# SCH_SX1262_Antenna.net
KiCad netlist of a schematic drawn in Altium Designer
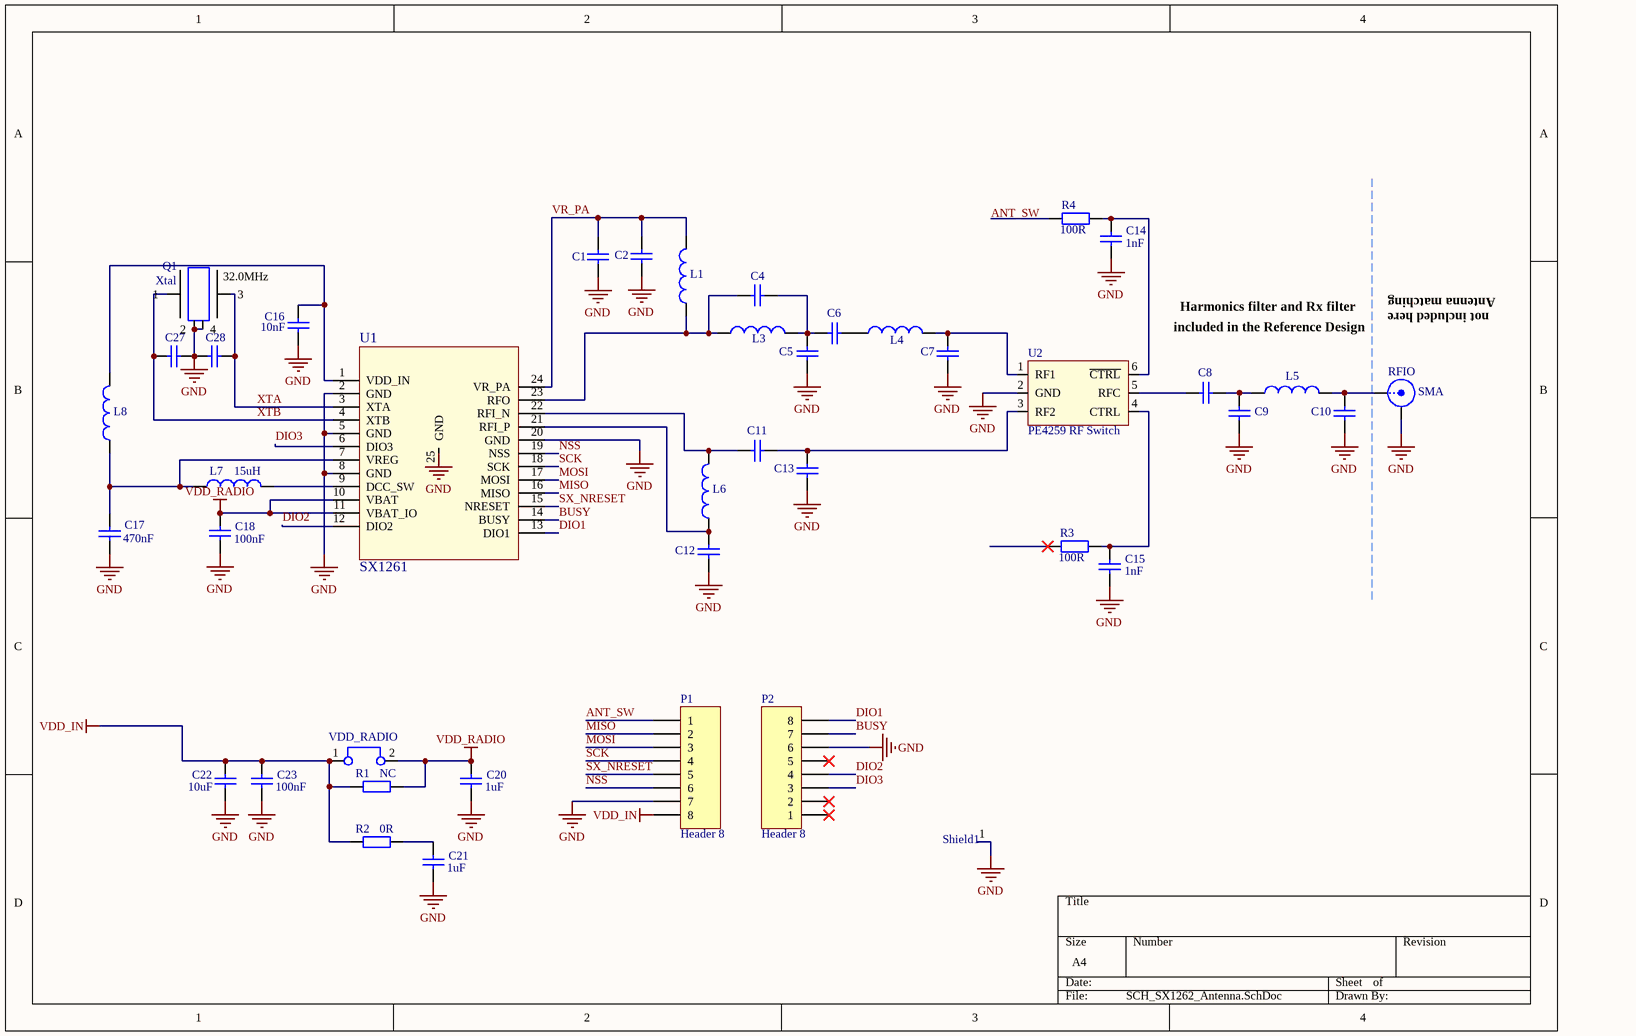
[diagram p0: SCH_SX1262_Antenna.SchDoc]

(export (version "E")
  (design (tool "Eeschema 10.0.6"))
  (components
    (comp (ref "C1")
      (value "Cap")
      (footprint "rlc_402_smd")
      (description "Capacitor SMD")
      (fields (field (name "PUBLISHER") "Altium Limited"))
      (libsource (lib "SX1261MB2xAS_e498v01a") (part "Cap"))
    )
    (comp (ref "C2")
      (value "Cap")
      (footprint "rlc_402_smd")
      (description "Capacitor SMD")
      (fields (field (name "PUBLISHER") "Altium Limited"))
      (libsource (lib "SX1261MB2xAS_e498v01a") (part "Cap"))
    )
    (comp (ref "C4")
      (value "Cap")
      (footprint "rlc_402_smd")
      (description "Capacitor SMD")
      (fields (field (name "PUBLISHER") "Altium Limited"))
      (libsource (lib "SX1261MB2xAS_e498v01a") (part "Cap"))
    )
    (comp (ref "C5")
      (value "Cap")
      (footprint "rlc_402_smd")
      (description "Capacitor SMD")
      (fields (field (name "PUBLISHER") "Altium Limited"))
      (libsource (lib "SX1261MB2xAS_e498v01a") (part "Cap"))
    )
    (comp (ref "C6")
      (value "Cap")
      (footprint "rlc_402_smd")
      (description "Capacitor SMD")
      (fields (field (name "PUBLISHER") "Altium Limited"))
      (libsource (lib "SX1261MB2xAS_e498v01a") (part "Cap"))
    )
    (comp (ref "C7")
      (value "Cap")
      (footprint "rlc_402_smd")
      (description "Capacitor SMD")
      (fields (field (name "PUBLISHER") "Altium Limited"))
      (libsource (lib "SX1261MB2xAS_e498v01a") (part "Cap"))
    )
    (comp (ref "C8")
      (value "Cap")
      (footprint "rlc_402_smd")
      (description "Capacitor SMD")
      (fields (field (name "PUBLISHER") "Altium Limited"))
      (libsource (lib "SX1261MB2xAS_e498v01a") (part "Cap"))
    )
    (comp (ref "C9")
      (value "Cap")
      (footprint "rlc_402_smd")
      (description "Capacitor SMD")
      (fields (field (name "PUBLISHER") "Altium Limited"))
      (libsource (lib "SX1261MB2xAS_e498v01a") (part "Cap"))
    )
    (comp (ref "C10")
      (value "Cap")
      (footprint "rlc_402_smd")
      (description "Capacitor SMD")
      (fields (field (name "PUBLISHER") "Altium Limited"))
      (libsource (lib "SX1261MB2xAS_e498v01a") (part "Cap"))
    )
    (comp (ref "C11")
      (value "Cap")
      (footprint "rlc_402_smd")
      (description "Capacitor SMD")
      (fields (field (name "PUBLISHER") "Altium Limited"))
      (libsource (lib "SX1261MB2xAS_e498v01a") (part "Cap"))
    )
    (comp (ref "C12")
      (value "Cap")
      (footprint "rlc_402_smd")
      (description "Capacitor SMD")
      (fields (field (name "PUBLISHER") "Altium Limited"))
      (libsource (lib "SX1261MB2xAS_e498v01a") (part "Cap"))
    )
    (comp (ref "C13")
      (value "Cap")
      (footprint "rlc_402_smd")
      (description "Capacitor SMD")
      (fields (field (name "PUBLISHER") "Altium Limited"))
      (libsource (lib "SX1261MB2xAS_e498v01a") (part "Cap"))
    )
    (comp (ref "C14")
      (value "1nF")
      (footprint "rlc_402_smd")
      (description "Capacitor SMD")
      (fields (field (name "Comment") "Cap") (field (name "PUBLISHER") "Altium Limited"))
      (libsource (lib "SX1261MB2xAS_e498v01a") (part "Cap"))
    )
    (comp (ref "C15")
      (value "1nF")
      (footprint "rlc_402_smd")
      (description "Capacitor SMD")
      (fields (field (name "Comment") "Cap") (field (name "PUBLISHER") "Altium Limited"))
      (libsource (lib "SX1261MB2xAS_e498v01a") (part "Cap"))
    )
    (comp (ref "C16")
      (value "10nF")
      (footprint "rlc_402_smd")
      (description "Capacitor SMD")
      (fields (field (name "Comment") "Cap") (field (name "PUBLISHER") "Altium Limited"))
      (libsource (lib "SX1261MB2xAS_e498v01a") (part "Cap"))
    )
    (comp (ref "C17")
      (value "470nF")
      (footprint "rlc_402_smd")
      (description "Capacitor SMD")
      (fields (field (name "Comment") "Cap") (field (name "PUBLISHER") "Altium Limited"))
      (libsource (lib "SX1261MB2xAS_e498v01a") (part "Cap"))
    )
    (comp (ref "C18")
      (value "100nF")
      (footprint "rlc_402_smd")
      (description "Capacitor SMD")
      (fields (field (name "Comment") "Cap") (field (name "PUBLISHER") "Altium Limited"))
      (libsource (lib "SX1261MB2xAS_e498v01a") (part "Cap"))
    )
    (comp (ref "C20")
      (value "1uF")
      (footprint "rlc_603_smd")
      (description "Capacitor SMD")
      (fields (field (name "Comment") "Cap") (field (name "PUBLISHER") "Altium Limited"))
      (libsource (lib "SX1261_e406v03a") (part "Cap"))
    )
    (comp (ref "C21")
      (value "1uF")
      (footprint "rlc_603_smd")
      (description "Capacitor SMD")
      (fields (field (name "Comment") "Cap") (field (name "PUBLISHER") "Altium Limited"))
      (libsource (lib "SX1261_e406v03a") (part "Cap"))
    )
    (comp (ref "C22")
      (value "10uF")
      (footprint "rlc_805_smd")
      (description "Capacitor SMD")
      (fields (field (name "Comment") "Cap") (field (name "PUBLISHER") "Altium Limited"))
      (libsource (lib "SX1261_e406v03a") (part "Cap"))
    )
    (comp (ref "C23")
      (value "100nF")
      (footprint "rlc_402_smd")
      (description "Capacitor SMD")
      (fields (field (name "Comment") "Cap") (field (name "PUBLISHER") "Altium Limited"))
      (libsource (lib "SX1261_e406v03a") (part "Cap"))
    )
    (comp (ref "C27")
      (value "Cap")
      (footprint "rlc_402_smd")
      (description "Capacitor SMD")
      (fields (field (name "PUBLISHER") "Altium Limited"))
      (libsource (lib "SX1261_e406v03a") (part "Cap"))
    )
    (comp (ref "C28")
      (value "Cap")
      (footprint "rlc_402_smd")
      (description "Capacitor SMD")
      (fields (field (name "PUBLISHER") "Altium Limited"))
      (libsource (lib "SX1261_e406v03a") (part "Cap"))
    )
    (comp (ref "L1")
      (value "Inductor")
      (footprint "rlc_402_smd")
      (description "Inductor SMD")
      (fields (field (name "PUBLISHER") "Altium Limited"))
      (libsource (lib "") (part "Inductor_1"))
    )
    (comp (ref "L3")
      (value "Inductor")
      (footprint "rlc_402_smd")
      (description "Inductor SMD")
      (fields (field (name "PUBLISHER") "Altium Limited"))
      (libsource (lib "") (part "Inductor_1"))
    )
    (comp (ref "L4")
      (value "Inductor")
      (footprint "rlc_402_smd")
      (description "Inductor SMD")
      (fields (field (name "PUBLISHER") "Altium Limited"))
      (libsource (lib "") (part "Inductor_1"))
    )
    (comp (ref "L5")
      (value "Inductor")
      (footprint "rlc_402_smd")
      (description "Inductor SMD")
      (fields (field (name "PUBLISHER") "Altium Limited"))
      (libsource (lib "") (part "Inductor_1"))
    )
    (comp (ref "L6")
      (value "Inductor")
      (footprint "rlc_402_smd")
      (description "Inductor SMD")
      (fields (field (name "PUBLISHER") "Altium Limited"))
      (libsource (lib "") (part "Inductor_1"))
    )
    (comp (ref "L7")
      (value "15uH")
      (footprint "rlc_805_smd enlarged")
      (description "Inductor SMD")
      (fields (field (name "Comment") "Inductor") (field (name "PUBLISHER") "Altium Limited"))
      (libsource (lib "") (part "Inductor_1"))
    )
    (comp (ref "L8")
      (value "Inductor")
      (footprint "rlc_402_smd")
      (description "Inductor SMD")
      (fields (field (name "PUBLISHER") "Altium Limited"))
      (libsource (lib "SX1261MB2xAS_e498v01a") (part "Inductor"))
    )
    (comp (ref "P1")
      (value "Header 8")
      (footprint "HDR1X8")
      (description "Header, 8-Pin")
      (fields (field (name "PUBLISHER") "Altium Limited"))
      (libsource (lib "") (part "Header 8_1"))
    )
    (comp (ref "P2")
      (value "Header 8")
      (footprint "HDR1X8")
      (description "Header, 8-Pin")
      (fields (field (name "PUBLISHER") "Altium Limited"))
      (libsource (lib "SX1262_DemoBoard") (part "Header 8"))
    )
    (comp (ref "Q1")
      (value "Xtal")
      (footprint "nd2016da")
      (description "Crystal with GND pins")
      (fields (field (name "ALTIUM_VALUE") "32.0MHz"))
      (libsource (lib "SX1261MB2xAS_e498v01a") (part "Xtal GND"))
    )
    (comp (ref "R1")
      (value "NC")
      (footprint "rlc_603_smd")
      (description "Resistor SMD - IEC symbol version")
      (fields (field (name "Comment") "Resistor"))
      (libsource (lib "SX1261_e406v03a") (part "Resistor"))
    )
    (comp (ref "R2")
      (value "0R")
      (footprint "rlc_603_smd")
      (description "Resistor SMD - IEC symbol version")
      (fields (field (name "Comment") "Resistor"))
      (libsource (lib "SX1261_e406v03a") (part "Resistor"))
    )
    (comp (ref "R3")
      (value "100R")
      (footprint "rlc_402_smd")
      (description "Resistor SMD - IEC symbol version")
      (fields (field (name "Comment") "Resistor"))
      (libsource (lib "SX1261MB2xAS_e498v01a") (part "Resistor"))
    )
    (comp (ref "R4")
      (value "100R")
      (footprint "rlc_402_smd")
      (description "Resistor SMD - IEC symbol version")
      (fields (field (name "Comment") "Resistor"))
      (libsource (lib "SX1261MB2xAS_e498v01a") (part "Resistor"))
    )
    (comp (ref "RFIO")
      (value "SMA")
      (footprint "SMA_end_launch_1.0mm_9.52mm")
      (description "SMA Straight Connector")
      (fields (field (name "PUBLISHER") "Altium Limited"))
      (libsource (lib "SX1261_e406v03a") (part "SMA"))
    )
    (comp (ref "Shield1")
      (value "Logo symbol")
      (footprint "BMIS-209-F - Shield")
      (description "Shield - EMI Gasket - Standard Surface Mount Shields")
      (libsource (lib "SX1261MB2xAS_e498v01a") (part "Shield"))
    )
    (comp (ref "U1")
      (value "SX1261")
      (footprint "vqfn24_4x4mm")
      (description "SX1261/2 - Ultra low power RF transceiver")
      (libsource (lib "SX1261MB2xAS_e498v01a") (part "SX126x"))
    )
    (comp (ref "U2")
      (value "PE4259 RF Switch")
      (footprint "SC70-6")
      (description "PE4259 Peregrine RF Switch")
      (libsource (lib "SX1261MB2xAS_e498v01a") (part "PE4259 RF Switch"))
    )
    (comp (ref "VDD_RADIO")
      (value "Jumper")
      (footprint "bridge_254mm")
      (description "Jumper Wire")
      (libsource (lib "SX1261_e406v03a") (part "Jumper"))
    )
  )
  (nets
    (net (code "1") (name "/ANT_SW") (class "Default")
      (node (ref "P1") (pin "1") (pinfunction "1_1") (pintype "passive"))
    )
    (net (code "2") (name "/BUSY") (class "Default")
      (node (ref "P2") (pin "7") (pinfunction "7_7") (pintype "passive"))
      (node (ref "U1") (pin "14") (pinfunction "BUSY_14") (pintype "passive"))
    )
    (net (code "3") (name "/DIO1") (class "Default")
      (node (ref "P2") (pin "8") (pinfunction "8_8") (pintype "passive"))
      (node (ref "U1") (pin "13") (pinfunction "DIO1_13") (pintype "passive"))
    )
    (net (code "4") (name "/DIO2") (class "Default")
      (node (ref "P2") (pin "4") (pinfunction "4_4") (pintype "passive"))
      (node (ref "U1") (pin "12") (pinfunction "DIO2_12") (pintype "passive"))
    )
    (net (code "5") (name "/DIO3") (class "Default")
      (node (ref "P2") (pin "3") (pinfunction "3_3") (pintype "passive"))
      (node (ref "U1") (pin "6") (pinfunction "DIO3_6") (pintype "passive"))
    )
    (net (code "6") (name "/MISO") (class "Default")
      (node (ref "P1") (pin "2") (pinfunction "2_2") (pintype "passive"))
      (node (ref "U1") (pin "16") (pinfunction "MISO_16") (pintype "passive"))
    )
    (net (code "7") (name "/MOSI") (class "Default")
      (node (ref "P1") (pin "3") (pinfunction "3_3") (pintype "passive"))
      (node (ref "U1") (pin "17") (pinfunction "MOSI_17") (pintype "passive"))
    )
    (net (code "8") (name "/NSS") (class "Default")
      (node (ref "P1") (pin "6") (pinfunction "6_6") (pintype "passive"))
      (node (ref "U1") (pin "19") (pinfunction "NSS_19") (pintype "passive"))
    )
    (net (code "9") (name "/SCK") (class "Default")
      (node (ref "P1") (pin "4") (pinfunction "4_4") (pintype "passive"))
      (node (ref "U1") (pin "18") (pinfunction "SCK_18") (pintype "passive"))
    )
    (net (code "10") (name "/SX_NRESET") (class "Default")
      (node (ref "P1") (pin "5") (pinfunction "5_5") (pintype "passive"))
      (node (ref "U1") (pin "15") (pinfunction "NRESET_15") (pintype "passive"))
    )
    (net (code "11") (name "/VR_PA") (class "Default")
      (node (ref "C1") (pin "2") (pinfunction "2_2") (pintype "passive"))
      (node (ref "C2") (pin "2") (pinfunction "2_2") (pintype "passive"))
      (node (ref "L1") (pin "2") (pinfunction "2_2") (pintype "passive"))
      (node (ref "U1") (pin "24") (pinfunction "VR_PA_24") (pintype "power_in"))
    )
    (net (code "12") (name "/XTA") (class "Default")
      (node (ref "C28") (pin "1") (pinfunction "1_1") (pintype "passive"))
      (node (ref "Q1") (pin "3") (pinfunction "3_3") (pintype "passive"))
      (node (ref "U1") (pin "3") (pinfunction "XTA_3") (pintype "passive"))
    )
    (net (code "13") (name "/XTB") (class "Default")
      (node (ref "C27") (pin "2") (pinfunction "2_2") (pintype "passive"))
      (node (ref "Q1") (pin "1") (pinfunction "1_1") (pintype "passive"))
      (node (ref "U1") (pin "4") (pinfunction "XTB_4") (pintype "passive"))
    )
    (net (code "14") (name "GND") (class "Default")
      (node (ref "C1") (pin "1") (pinfunction "1_1") (pintype "passive"))
      (node (ref "C10") (pin "1") (pinfunction "1_1") (pintype "passive"))
      (node (ref "C12") (pin "1") (pinfunction "1_1") (pintype "passive"))
      (node (ref "C13") (pin "1") (pinfunction "1_1") (pintype "passive"))
      (node (ref "C14") (pin "2") (pinfunction "2_2") (pintype "passive"))
      (node (ref "C15") (pin "2") (pinfunction "2_2") (pintype "passive"))
      (node (ref "C16") (pin "1") (pinfunction "1_1") (pintype "passive"))
      (node (ref "C17") (pin "1") (pinfunction "1_1") (pintype "passive"))
      (node (ref "C18") (pin "1") (pinfunction "1_1") (pintype "passive"))
      (node (ref "C2") (pin "1") (pinfunction "1_1") (pintype "passive"))
      (node (ref "C20") (pin "1") (pinfunction "1_1") (pintype "passive"))
      (node (ref "C21") (pin "1") (pinfunction "1_1") (pintype "passive"))
      (node (ref "C22") (pin "1") (pinfunction "1_1") (pintype "passive"))
      (node (ref "C23") (pin "1") (pinfunction "1_1") (pintype "passive"))
      (node (ref "C27") (pin "1") (pinfunction "1_1") (pintype "passive"))
      (node (ref "C28") (pin "2") (pinfunction "2_2") (pintype "passive"))
      (node (ref "C5") (pin "1") (pinfunction "1_1") (pintype "passive"))
      (node (ref "C7") (pin "1") (pinfunction "1_1") (pintype "passive"))
      (node (ref "C9") (pin "1") (pinfunction "1_1") (pintype "passive"))
      (node (ref "P1") (pin "7") (pinfunction "7_7") (pintype "passive"))
      (node (ref "P2") (pin "6") (pinfunction "6_6") (pintype "passive"))
      (node (ref "Q1") (pin "2") (pinfunction "2_2") (pintype "passive"))
      (node (ref "Q1") (pin "4") (pinfunction "4_4") (pintype "passive"))
      (node (ref "RFIO") (pin "2") (pinfunction "GND_2") (pintype "passive"))
      (node (ref "Shield1") (pin "1") (pinfunction "1_1") (pintype "passive"))
      (node (ref "U1") (pin "2") (pinfunction "GND_2") (pintype "passive"))
      (node (ref "U1") (pin "20") (pinfunction "GND_20") (pintype "passive"))
      (node (ref "U1") (pin "25") (pinfunction "GND_25") (pintype "passive"))
      (node (ref "U1") (pin "5") (pinfunction "GND_5") (pintype "passive"))
      (node (ref "U1") (pin "8") (pinfunction "GND_8") (pintype "passive"))
      (node (ref "U2") (pin "2") (pinfunction "GND_2") (pintype "passive"))
    )
    (net (code "15") (name "Net-(C4-Pad1)") (class "Default")
      (node (ref "C4") (pin "1") (pinfunction "1_1") (pintype "passive"))
      (node (ref "C5") (pin "2") (pinfunction "2_2") (pintype "passive"))
      (node (ref "C6") (pin "2") (pinfunction "2_2") (pintype "passive"))
      (node (ref "L3") (pin "2") (pinfunction "2_2") (pintype "passive"))
    )
    (net (code "16") (name "Net-(C6-Pad1)") (class "Default")
      (node (ref "C6") (pin "1") (pinfunction "1_1") (pintype "passive"))
      (node (ref "L4") (pin "1") (pinfunction "1_1") (pintype "passive"))
    )
    (net (code "17") (name "Net-(C8-Pad1)") (class "Default")
      (node (ref "C8") (pin "1") (pinfunction "1_1") (pintype "passive"))
      (node (ref "C9") (pin "2") (pinfunction "2_2") (pintype "passive"))
      (node (ref "L5") (pin "1") (pinfunction "1_1") (pintype "passive"))
    )
    (net (code "18") (name "Net-(C21-Pad2)") (class "Default")
      (node (ref "C21") (pin "2") (pinfunction "2_2") (pintype "passive"))
      (node (ref "R2") (pin "1") (pinfunction "1_1") (pintype "passive"))
    )
    (net (code "19") (name "Net-(RFIO-Signal)") (class "Default")
      (node (ref "C10") (pin "2") (pinfunction "2_2") (pintype "passive"))
      (node (ref "L5") (pin "2") (pinfunction "2_2") (pintype "passive"))
      (node (ref "RFIO") (pin "1") (pinfunction "Signal_1") (pintype "passive"))
    )
    (net (code "20") (name "Net-(U1-DCC_SW)") (class "Default")
      (node (ref "L7") (pin "2") (pinfunction "2_2") (pintype "passive"))
      (node (ref "U1") (pin "9") (pinfunction "DCC_SW_9") (pintype "power_in"))
    )
    (net (code "21") (name "Net-(U1-RFI_N)") (class "Default")
      (node (ref "C11") (pin "2") (pinfunction "2_2") (pintype "passive"))
      (node (ref "L6") (pin "2") (pinfunction "2_2") (pintype "passive"))
      (node (ref "U1") (pin "22") (pinfunction "RFI_N_22") (pintype "passive"))
    )
    (net (code "22") (name "Net-(U1-RFI_P)") (class "Default")
      (node (ref "C12") (pin "2") (pinfunction "2_2") (pintype "passive"))
      (node (ref "L6") (pin "1") (pinfunction "1_1") (pintype "passive"))
      (node (ref "U1") (pin "21") (pinfunction "RFI_P_21") (pintype "passive"))
    )
    (net (code "23") (name "Net-(U1-RFO)") (class "Default")
      (node (ref "C4") (pin "2") (pinfunction "2_2") (pintype "passive"))
      (node (ref "L1") (pin "1") (pinfunction "1_1") (pintype "passive"))
      (node (ref "L3") (pin "1") (pinfunction "1_1") (pintype "passive"))
      (node (ref "U1") (pin "23") (pinfunction "RFO_23") (pintype "passive"))
    )
    (net (code "24") (name "Net-(U1-VDD_IN)") (class "Default")
      (node (ref "C16") (pin "2") (pinfunction "2_2") (pintype "passive"))
      (node (ref "L8") (pin "1") (pinfunction "1_1") (pintype "passive"))
      (node (ref "U1") (pin "1") (pinfunction "VDD_IN_1") (pintype "power_in"))
    )
    (net (code "25") (name "Net-(U1-VREG)") (class "Default")
      (node (ref "C17") (pin "2") (pinfunction "2_2") (pintype "passive"))
      (node (ref "L7") (pin "1") (pinfunction "1_1") (pintype "passive"))
      (node (ref "L8") (pin "2") (pinfunction "2_2") (pintype "passive"))
      (node (ref "U1") (pin "7") (pinfunction "VREG_7") (pintype "power_in"))
    )
    (net (code "26") (name "Net-(U2-CTRL)") (class "Default")
      (node (ref "C15") (pin "1") (pinfunction "1_1") (pintype "passive"))
      (node (ref "R3") (pin "1") (pinfunction "1_1") (pintype "passive"))
      (node (ref "U2") (pin "4") (pinfunction "CTRL_4") (pintype "passive"))
    )
    (net (code "27") (name "Net-(U2-RF1)") (class "Default")
      (node (ref "C7") (pin "2") (pinfunction "2_2") (pintype "passive"))
      (node (ref "L4") (pin "2") (pinfunction "2_2") (pintype "passive"))
      (node (ref "U2") (pin "1") (pinfunction "RF1_1") (pintype "passive"))
    )
    (net (code "28") (name "Net-(U2-RF2)") (class "Default")
      (node (ref "C11") (pin "1") (pinfunction "1_1") (pintype "passive"))
      (node (ref "C13") (pin "2") (pinfunction "2_2") (pintype "passive"))
      (node (ref "U2") (pin "3") (pinfunction "RF2_3") (pintype "passive"))
    )
    (net (code "29") (name "Net-(U2-RFC)") (class "Default")
      (node (ref "C8") (pin "2") (pinfunction "2_2") (pintype "passive"))
      (node (ref "U2") (pin "5") (pinfunction "RFC_5") (pintype "passive"))
    )
    (net (code "30") (name "Net-(U2-~{CTRL})") (class "Default")
      (node (ref "C14") (pin "1") (pinfunction "1_1") (pintype "passive"))
      (node (ref "R4") (pin "1") (pinfunction "1_1") (pintype "passive"))
      (node (ref "U2") (pin "6") (pinfunction "~{CTRL}_6") (pintype "passive"))
    )
    (net (code "31") (name "VDD_IN") (class "Default")
      (node (ref "C22") (pin "2") (pinfunction "2_2") (pintype "passive"))
      (node (ref "C23") (pin "2") (pinfunction "2_2") (pintype "passive"))
      (node (ref "P1") (pin "8") (pinfunction "8_8") (pintype "passive"))
      (node (ref "R1") (pin "2") (pinfunction "2_2") (pintype "passive"))
      (node (ref "R2") (pin "2") (pinfunction "2_2") (pintype "passive"))
      (node (ref "VDD_RADIO") (pin "1") (pinfunction "1_1") (pintype "passive"))
    )
    (net (code "32") (name "VDD_RADIO") (class "Default")
      (node (ref "C18") (pin "2") (pinfunction "2_2") (pintype "passive"))
      (node (ref "C20") (pin "2") (pinfunction "2_2") (pintype "passive"))
      (node (ref "R1") (pin "1") (pinfunction "1_1") (pintype "passive"))
      (node (ref "U1") (pin "10") (pinfunction "VBAT_10") (pintype "power_in"))
      (node (ref "U1") (pin "11") (pinfunction "VBAT_IO_11") (pintype "power_in"))
      (node (ref "VDD_RADIO") (pin "2") (pinfunction "2_2") (pintype "passive"))
    )
    (net (code "33") (name "unconnected-(P2-Pad1)") (class "Default")
      (node (ref "P2") (pin "1") (pinfunction "1_1") (pintype "passive+no_connect"))
    )
    (net (code "34") (name "unconnected-(P2-Pad2)") (class "Default")
      (node (ref "P2") (pin "2") (pinfunction "2_2") (pintype "passive+no_connect"))
    )
    (net (code "35") (name "unconnected-(P2-Pad5)") (class "Default")
      (node (ref "P2") (pin "5") (pinfunction "5_5") (pintype "passive+no_connect"))
    )
    (net (code "36") (name "unconnected-(R3-Pad2)") (class "Default")
      (node (ref "R3") (pin "2") (pinfunction "2_2") (pintype "passive+no_connect"))
    )
    (net (code "37") (name "unconnected-(R4-Pad2)") (class "Default")
      (node (ref "R4") (pin "2") (pinfunction "2_2") (pintype "passive"))
    )
  )
)
